# Jetson_power.net
KiCad netlist of a schematic drawn in Altium Designer
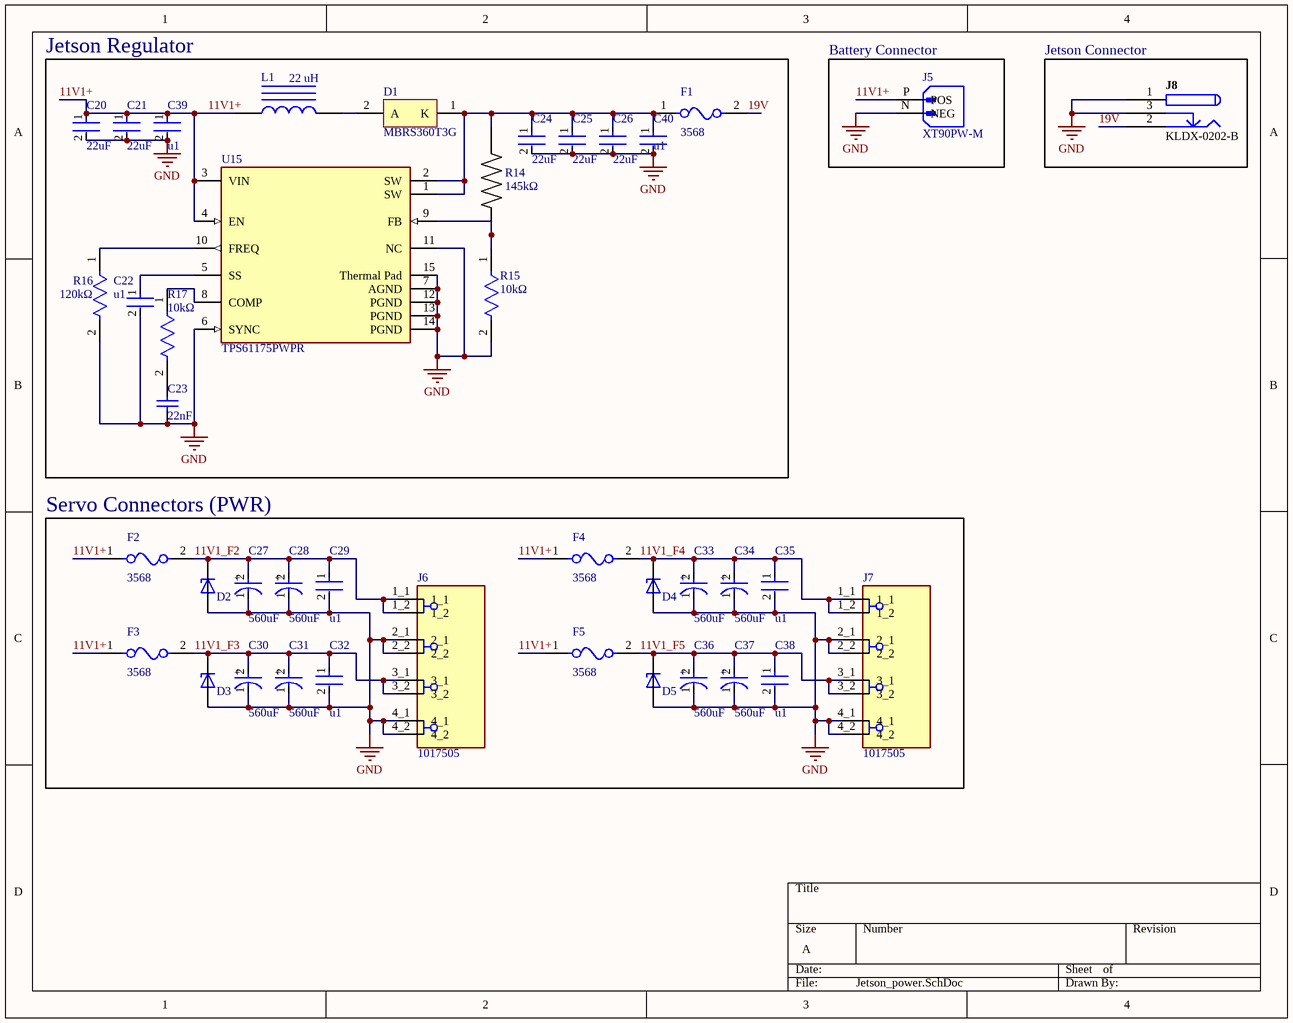
[diagram p0: Jetson_power.SchDoc]

(export (version "E")
  (design (tool "Eeschema 10.0.6"))
  (components
    (comp (ref "C20")
      (value "22uF")
      (footprint "FP-CGA9P-MFG")
      (description "CAP 2220 X7R 50V 22UF 20% 2.50MM CGA9P3X7R1H226M250KB")
      (libsource (lib "Altium Content Vault") (part "b4654b650e69147ec39a6b967a45e02"))
    )
    (comp (ref "C21")
      (value "22uF")
      (footprint "FP-CGA9P-MFG")
      (description "CAP 2220 X7R 50V 22UF 20% 2.50MM CGA9P3X7R1H226M250KB")
      (libsource (lib "Altium Content Vault") (part "b4654b650e69147ec39a6b967a45e02"))
    )
    (comp (ref "C22")
      (value "u1")
      (footprint "FP-CC0805-0_85-MFG")
      (description "CC0805KRX7R9BB104 CAP CER 0.1UF 50V X7R 0805")
      (fields (field (name "TOLERANCE") "0.1") (field (name "MANUFACTURER PART NUMBER") "CC0805KRX7R9BB104"))
      (libsource (lib "Altium Content Vault") (part "11868f565c42a9108669ba33697ecf6"))
    )
    (comp (ref "C23")
      (value "22nF")
      (footprint "CAPC2013X94X50ML20T25")
      (description "08055C223KAZ2A")
      (fields (field (name "MANUFACTURER") "AVX Interconnect / Elco"))
      (libsource (lib "Altium Content Vault") (part "CAP"))
    )
    (comp (ref "C24")
      (value "22uF")
      (footprint "FP-CGA9P-MFG")
      (description "CAP 2220 X7R 50V 22UF 20% 2.50MM CGA9P3X7R1H226M250KB")
      (libsource (lib "Altium Content Vault") (part "b4654b650e69147ec39a6b967a45e02"))
    )
    (comp (ref "C25")
      (value "22uF")
      (footprint "FP-CGA9P-MFG")
      (description "CAP 2220 X7R 50V 22UF 20% 2.50MM CGA9P3X7R1H226M250KB")
      (libsource (lib "Altium Content Vault") (part "b4654b650e69147ec39a6b967a45e02"))
    )
    (comp (ref "C26")
      (value "22uF")
      (footprint "FP-CGA9P-MFG")
      (description "CAP 2220 X7R 50V 22UF 20% 2.50MM CGA9P3X7R1H226M250KB")
      (libsource (lib "Altium Content Vault") (part "b4654b650e69147ec39a6b967a45e02"))
    )
    (comp (ref "C27")
      (value "560uF")
      (footprint "FP-OS-CON-TH-E12-d_0_6-MFG")
      (description "Conductive Polymer Aluminum Solid Capacitors (OS-CON) 560uF ±20% 16V RADIAL TH 8x12mm 16SEPF560M")
      (fields (field (name "TOLERANCE") "20%") (field (name "VOLTAGE") "16V"))
      (libsource (lib "Altium Content Vault") (part "203bc49f2ac43e59fd269a8c329ed05"))
    )
    (comp (ref "C28")
      (value "560uF")
      (footprint "FP-OS-CON-TH-E12-d_0_6-MFG")
      (description "Conductive Polymer Aluminum Solid Capacitors (OS-CON) 560uF ±20% 16V RADIAL TH 8x12mm 16SEPF560M")
      (fields (field (name "TOLERANCE") "20%") (field (name "VOLTAGE") "16V"))
      (libsource (lib "Altium Content Vault") (part "203bc49f2ac43e59fd269a8c329ed05"))
    )
    (comp (ref "C29")
      (value "u1")
      (footprint "FP-CC0805-0_85-MFG")
      (description "CC0805KRX7R9BB104 CAP CER 0.1UF 50V X7R 0805")
      (fields (field (name "TOLERANCE") "0.1") (field (name "MANUFACTURER PART NUMBER") "CC0805KRX7R9BB104"))
      (libsource (lib "Altium Content Vault") (part "11868f565c42a9108669ba33697ecf6"))
    )
    (comp (ref "C30")
      (value "560uF")
      (footprint "FP-OS-CON-TH-E12-d_0_6-MFG")
      (description "Conductive Polymer Aluminum Solid Capacitors (OS-CON) 560uF ±20% 16V RADIAL TH 8x12mm 16SEPF560M")
      (fields (field (name "TOLERANCE") "20%") (field (name "VOLTAGE") "16V"))
      (libsource (lib "Altium Content Vault") (part "203bc49f2ac43e59fd269a8c329ed05"))
    )
    (comp (ref "C31")
      (value "560uF")
      (footprint "FP-OS-CON-TH-E12-d_0_6-MFG")
      (description "Conductive Polymer Aluminum Solid Capacitors (OS-CON) 560uF ±20% 16V RADIAL TH 8x12mm 16SEPF560M")
      (fields (field (name "TOLERANCE") "20%") (field (name "VOLTAGE") "16V"))
      (libsource (lib "Altium Content Vault") (part "203bc49f2ac43e59fd269a8c329ed05"))
    )
    (comp (ref "C32")
      (value "u1")
      (footprint "FP-CC0805-0_85-MFG")
      (description "CC0805KRX7R9BB104 CAP CER 0.1UF 50V X7R 0805")
      (fields (field (name "TOLERANCE") "0.1") (field (name "MANUFACTURER PART NUMBER") "CC0805KRX7R9BB104"))
      (libsource (lib "Altium Content Vault") (part "11868f565c42a9108669ba33697ecf6"))
    )
    (comp (ref "C33")
      (value "560uF")
      (footprint "FP-OS-CON-TH-E12-d_0_6-MFG")
      (description "Conductive Polymer Aluminum Solid Capacitors (OS-CON) 560uF ±20% 16V RADIAL TH 8x12mm 16SEPF560M")
      (fields (field (name "TOLERANCE") "20%") (field (name "VOLTAGE") "16V"))
      (libsource (lib "Altium Content Vault") (part "203bc49f2ac43e59fd269a8c329ed05"))
    )
    (comp (ref "C34")
      (value "560uF")
      (footprint "FP-OS-CON-TH-E12-d_0_6-MFG")
      (description "Conductive Polymer Aluminum Solid Capacitors (OS-CON) 560uF ±20% 16V RADIAL TH 8x12mm 16SEPF560M")
      (fields (field (name "TOLERANCE") "20%") (field (name "VOLTAGE") "16V"))
      (libsource (lib "Altium Content Vault") (part "203bc49f2ac43e59fd269a8c329ed05"))
    )
    (comp (ref "C35")
      (value "u1")
      (footprint "FP-CC0805-0_85-MFG")
      (description "CC0805KRX7R9BB104 CAP CER 0.1UF 50V X7R 0805")
      (fields (field (name "TOLERANCE") "0.1") (field (name "MANUFACTURER PART NUMBER") "CC0805KRX7R9BB104"))
      (libsource (lib "Altium Content Vault") (part "11868f565c42a9108669ba33697ecf6"))
    )
    (comp (ref "C36")
      (value "560uF")
      (footprint "FP-OS-CON-TH-E12-d_0_6-MFG")
      (description "Conductive Polymer Aluminum Solid Capacitors (OS-CON) 560uF ±20% 16V RADIAL TH 8x12mm 16SEPF560M")
      (fields (field (name "TOLERANCE") "20%") (field (name "VOLTAGE") "16V"))
      (libsource (lib "Altium Content Vault") (part "203bc49f2ac43e59fd269a8c329ed05"))
    )
    (comp (ref "C37")
      (value "560uF")
      (footprint "FP-OS-CON-TH-E12-d_0_6-MFG")
      (description "Conductive Polymer Aluminum Solid Capacitors (OS-CON) 560uF ±20% 16V RADIAL TH 8x12mm 16SEPF560M")
      (fields (field (name "TOLERANCE") "20%") (field (name "VOLTAGE") "16V"))
      (libsource (lib "Altium Content Vault") (part "203bc49f2ac43e59fd269a8c329ed05"))
    )
    (comp (ref "C38")
      (value "u1")
      (footprint "FP-CC0805-0_85-MFG")
      (description "CC0805KRX7R9BB104 CAP CER 0.1UF 50V X7R 0805")
      (fields (field (name "TOLERANCE") "0.1") (field (name "MANUFACTURER PART NUMBER") "CC0805KRX7R9BB104"))
      (libsource (lib "Altium Content Vault") (part "11868f565c42a9108669ba33697ecf6"))
    )
    (comp (ref "C39")
      (value "u1")
      (footprint "FP-CC0805-0_85-MFG")
      (description "CC0805KRX7R9BB104 CAP CER 0.1UF 50V X7R 0805")
      (fields (field (name "TOLERANCE") "0.1") (field (name "MANUFACTURER PART NUMBER") "CC0805KRX7R9BB104"))
      (libsource (lib "Altium Content Vault") (part "11868f565c42a9108669ba33697ecf6"))
    )
    (comp (ref "C40")
      (value "u1")
      (footprint "FP-CC0805-0_85-MFG")
      (description "CC0805KRX7R9BB104 CAP CER 0.1UF 50V X7R 0805")
      (fields (field (name "TOLERANCE") "0.1") (field (name "MANUFACTURER PART NUMBER") "CC0805KRX7R9BB104"))
      (libsource (lib "Altium Content Vault") (part "11868f565c42a9108669ba33697ecf6"))
    )
    (comp (ref "D1")
      (value "MBRS360T3G")
      (footprint "ONSC-SMC-2-403-03_V")
      (description "Schottky Power Rectifier, 2-Pin SMC, Pb-Free, Tape and Reel")
      (fields (field (name "MANUFACTURER") "On Semiconductor"))
      (libsource (lib "Altium Content Vault") (part "ONSC-D-K1A2-2_A"))
    )
    (comp (ref "D2")
      (value "SMBJ13A-13-F")
      (footprint "DIOM5336X250N")
      (description "400 W 13 V Uni-Directional SMT Transient Voltage Suppressor Diode - DO-214AA")
      (fields (field (name "MF") "Diodes Inc."))
      (libsource (lib "Bryan Heddle") (part "SMBJ13A-13-F"))
    )
    (comp (ref "D3")
      (value "SMBJ13A-13-F")
      (footprint "DIOM5336X250N")
      (description "400 W 13 V Uni-Directional SMT Transient Voltage Suppressor Diode - DO-214AA")
      (fields (field (name "MF") "Diodes Inc."))
      (libsource (lib "Bryan Heddle") (part "SMBJ13A-13-F"))
    )
    (comp (ref "D4")
      (value "SMBJ13A-13-F")
      (footprint "DIOM5336X250N")
      (description "400 W 13 V Uni-Directional SMT Transient Voltage Suppressor Diode - DO-214AA")
      (fields (field (name "MF") "Diodes Inc."))
      (libsource (lib "Bryan Heddle") (part "SMBJ13A-13-F"))
    )
    (comp (ref "D5")
      (value "SMBJ13A-13-F")
      (footprint "DIOM5336X250N")
      (description "400 W 13 V Uni-Directional SMT Transient Voltage Suppressor Diode - DO-214AA")
      (fields (field (name "MF") "Diodes Inc."))
      (libsource (lib "Bryan Heddle") (part "SMBJ13A-13-F"))
    )
    (comp (ref "F1")
      (value "3568")
      (footprint "FP-3568-MFG")
      (fields (field (name "VOLTAGE") "500V"))
      (libsource (lib "Altium Content Vault") (part "3568"))
    )
    (comp (ref "F2")
      (value "3568")
      (footprint "FP-3568-MFG")
      (fields (field (name "VOLTAGE") "500V"))
      (libsource (lib "Altium Content Vault") (part "3568"))
    )
    (comp (ref "F3")
      (value "3568")
      (footprint "FP-3568-MFG")
      (fields (field (name "VOLTAGE") "500V"))
      (libsource (lib "Altium Content Vault") (part "3568"))
    )
    (comp (ref "F4")
      (value "3568")
      (footprint "FP-3568-MFG")
      (fields (field (name "VOLTAGE") "500V"))
      (libsource (lib "Altium Content Vault") (part "3568"))
    )
    (comp (ref "F5")
      (value "3568")
      (footprint "FP-3568-MFG")
      (fields (field (name "VOLTAGE") "500V"))
      (libsource (lib "Altium Content Vault") (part "3568"))
    )
    (comp (ref "J5")
      (value "XT90PW-M")
      (footprint "AMASS_XT90PW-M - duplicate")
      (description "Socket; DC supply; XT90; male; PIN: 2; on PCBs; THT; Colour: yellow")
      (fields (field (name "MF") "AMASS"))
      (libsource (lib "AI_Project_Library") (part "XT90PW-M"))
    )
    (comp (ref "J6")
      (value "1017505")
      (footprint "PHOENIX_1017505")
      (fields (field (name "MF") "{'manufacturer': u'Phoenix Contact'}"))
      (libsource (lib "Bryan Heddle") (part "1017505"))
    )
    (comp (ref "J7")
      (value "1017505")
      (footprint "PHOENIX_1017505")
      (fields (field (name "MF") "{'manufacturer': u'Phoenix Contact'}"))
      (libsource (lib "Bryan Heddle") (part "1017505"))
    )
    (comp (ref "J8")
      (value "KLDX-0202-B")
      (footprint "KYCN-KLDX-0202-B_V")
      (description "3 Conductor Power Jack, 2 break 2 aux contacts")
      (libsource (lib "Altium Content Vault") (part "KYCN-KLDX-0202-B-3"))
    )
    (comp (ref "L1")
      (value "22 uH")
      (footprint "COIL-MSS1038_V")
      (description "XAL7070")
      (fields (field (name "TOLERANCE") "20%") (field (name "MANUFACTURER") "Coilcraft"))
      (libsource (lib "Altium Content Vault") (part "IND-DOT-2_A"))
    )
    (comp (ref "R14")
      (value "145kΩ")
      (footprint "*RESC2012X60N")
      (description "RN73H2ATTD1453B25")
      (libsource (lib "AI_Project_Library") (part "RN73H2ATTD1453B25"))
    )
    (comp (ref "R15")
      (value "10kΩ")
      (footprint "FP-RNCP0805-IPC_C")
      (description "10kΩ ±1% 0.25W 0805 High Power Anti-Sulfur Thin Film Chip Resistor RNCP0805FTD10K0")
      (fields (field (name "TOLERANCE") "1%"))
      (libsource (lib "Altium Content Vault") (part "1029c3af85768c4190bb7ad29bc67b5"))
    )
    (comp (ref "R16")
      (value "120kΩ")
      (footprint "FP-RMCF0603-IPC_A")
      (description "120kΩ ±1% 0.1W 0603 Thick Film Chip Resistor AEC-Q200 compliant RMCF0603FG120K")
      (fields (field (name "TOLERANCE") "1%"))
      (libsource (lib "Altium Content Vault") (part "1029c3af85768c4190bb7ad29bc67b5"))
    )
    (comp (ref "R17")
      (value "10kΩ")
      (footprint "FP-RNCP0805-IPC_C")
      (description "10kΩ ±1% 0.25W 0805 High Power Anti-Sulfur Thin Film Chip Resistor RNCP0805FTD10K0")
      (fields (field (name "TOLERANCE") "1%"))
      (libsource (lib "Altium Content Vault") (part "1029c3af85768c4190bb7ad29bc67b5"))
    )
    (comp (ref "U15")
      (value "TPS61175PWPR")
      (footprint "FP-PWP0014E-MFG")
      (description "IC REG MULT CONFIG ADJ 14HTSSOP")
      (fields
        (field (name "OCTOPART") "https://octopart.com/tps61175pwpr-texas+instruments-12190773")
        (field (name "MANUFACTURER") "Texas Instruments")
      )
      (libsource (lib "Altium Content Vault") (part "f47c98dbe7414c9a8c87baa7f0ed8c9"))
    )
  )
  (nets
    (net (code "1") (name "/11V1+") (class "Default")
      (node (ref "C20") (pin "1") (pinfunction "1_1") (pintype "passive"))
      (node (ref "C21") (pin "1") (pinfunction "1_1") (pintype "passive"))
      (node (ref "C39") (pin "1") (pinfunction "1_1") (pintype "passive"))
      (node (ref "F2") (pin "1") (pinfunction "1_1") (pintype "passive"))
      (node (ref "F3") (pin "1") (pinfunction "1_1") (pintype "passive"))
      (node (ref "F4") (pin "1") (pinfunction "1_1") (pintype "passive"))
      (node (ref "F5") (pin "1") (pinfunction "1_1") (pintype "passive"))
      (node (ref "J5") (pin "P") (pinfunction "POS_P") (pintype "passive"))
      (node (ref "L1") (pin "1") (pinfunction "1_1") (pintype "passive"))
      (node (ref "U15") (pin "3") (pinfunction "VIN_3") (pintype "power_in"))
      (node (ref "U15") (pin "4") (pinfunction "EN_4") (pintype "input"))
    )
    (net (code "2") (name "/11V1_F2") (class "Default")
      (node (ref "C27") (pin "2") (pinfunction "A_2") (pintype "passive"))
      (node (ref "C28") (pin "2") (pinfunction "A_2") (pintype "passive"))
      (node (ref "C29") (pin "1") (pinfunction "1_1") (pintype "passive"))
      (node (ref "D2") (pin "1") (pinfunction "C_1") (pintype "passive"))
      (node (ref "F2") (pin "2") (pinfunction "2_2") (pintype "passive"))
      (node (ref "J6") (pin "1_1") (pinfunction "1_1_1_1") (pintype "passive"))
      (node (ref "J6") (pin "1_2") (pinfunction "1_2_1_2") (pintype "passive"))
    )
    (net (code "3") (name "/11V1_F3") (class "Default")
      (node (ref "C30") (pin "2") (pinfunction "A_2") (pintype "passive"))
      (node (ref "C31") (pin "2") (pinfunction "A_2") (pintype "passive"))
      (node (ref "C32") (pin "1") (pinfunction "1_1") (pintype "passive"))
      (node (ref "D3") (pin "1") (pinfunction "C_1") (pintype "passive"))
      (node (ref "F3") (pin "2") (pinfunction "2_2") (pintype "passive"))
      (node (ref "J6") (pin "3_1") (pinfunction "3_1_3_1") (pintype "passive"))
      (node (ref "J6") (pin "3_2") (pinfunction "3_2_3_2") (pintype "passive"))
    )
    (net (code "4") (name "/11V1_F4") (class "Default")
      (node (ref "C33") (pin "2") (pinfunction "A_2") (pintype "passive"))
      (node (ref "C34") (pin "2") (pinfunction "A_2") (pintype "passive"))
      (node (ref "C35") (pin "1") (pinfunction "1_1") (pintype "passive"))
      (node (ref "D4") (pin "1") (pinfunction "C_1") (pintype "passive"))
      (node (ref "F4") (pin "2") (pinfunction "2_2") (pintype "passive"))
      (node (ref "J7") (pin "1_1") (pinfunction "1_1_1_1") (pintype "passive"))
      (node (ref "J7") (pin "1_2") (pinfunction "1_2_1_2") (pintype "passive"))
    )
    (net (code "5") (name "/11V1_F5") (class "Default")
      (node (ref "C36") (pin "2") (pinfunction "A_2") (pintype "passive"))
      (node (ref "C37") (pin "2") (pinfunction "A_2") (pintype "passive"))
      (node (ref "C38") (pin "1") (pinfunction "1_1") (pintype "passive"))
      (node (ref "D5") (pin "1") (pinfunction "C_1") (pintype "passive"))
      (node (ref "F5") (pin "2") (pinfunction "2_2") (pintype "passive"))
      (node (ref "J7") (pin "3_1") (pinfunction "3_1_3_1") (pintype "passive"))
      (node (ref "J7") (pin "3_2") (pinfunction "3_2_3_2") (pintype "passive"))
    )
    (net (code "6") (name "/19V") (class "Default")
      (node (ref "F1") (pin "2") (pinfunction "2_2") (pintype "passive"))
      (node (ref "J8") (pin "2") (pintype "power_in"))
    )
    (net (code "7") (name "GND") (class "Default")
      (node (ref "C20") (pin "2") (pinfunction "2_2") (pintype "passive"))
      (node (ref "C21") (pin "2") (pinfunction "2_2") (pintype "passive"))
      (node (ref "C22") (pin "2") (pinfunction "2_2") (pintype "passive"))
      (node (ref "C23") (pin "1") (pinfunction "1_1") (pintype "passive"))
      (node (ref "C24") (pin "2") (pinfunction "2_2") (pintype "passive"))
      (node (ref "C25") (pin "2") (pinfunction "2_2") (pintype "passive"))
      (node (ref "C26") (pin "2") (pinfunction "2_2") (pintype "passive"))
      (node (ref "C27") (pin "1") (pinfunction "C_1") (pintype "passive"))
      (node (ref "C28") (pin "1") (pinfunction "C_1") (pintype "passive"))
      (node (ref "C29") (pin "2") (pinfunction "2_2") (pintype "passive"))
      (node (ref "C30") (pin "1") (pinfunction "C_1") (pintype "passive"))
      (node (ref "C31") (pin "1") (pinfunction "C_1") (pintype "passive"))
      (node (ref "C32") (pin "2") (pinfunction "2_2") (pintype "passive"))
      (node (ref "C33") (pin "1") (pinfunction "C_1") (pintype "passive"))
      (node (ref "C34") (pin "1") (pinfunction "C_1") (pintype "passive"))
      (node (ref "C35") (pin "2") (pinfunction "2_2") (pintype "passive"))
      (node (ref "C36") (pin "1") (pinfunction "C_1") (pintype "passive"))
      (node (ref "C37") (pin "1") (pinfunction "C_1") (pintype "passive"))
      (node (ref "C38") (pin "2") (pinfunction "2_2") (pintype "passive"))
      (node (ref "C39") (pin "2") (pinfunction "2_2") (pintype "passive"))
      (node (ref "C40") (pin "2") (pinfunction "2_2") (pintype "passive"))
      (node (ref "D2") (pin "2") (pinfunction "A_2") (pintype "passive"))
      (node (ref "D3") (pin "2") (pinfunction "A_2") (pintype "passive"))
      (node (ref "D4") (pin "2") (pinfunction "A_2") (pintype "passive"))
      (node (ref "D5") (pin "2") (pinfunction "A_2") (pintype "passive"))
      (node (ref "J5") (pin "N") (pinfunction "NEG_N") (pintype "passive"))
      (node (ref "J6") (pin "2_1") (pinfunction "2_1_2_1") (pintype "passive"))
      (node (ref "J6") (pin "2_2") (pinfunction "2_2_2_2") (pintype "passive"))
      (node (ref "J6") (pin "4_1") (pinfunction "4_1_4_1") (pintype "passive"))
      (node (ref "J6") (pin "4_2") (pinfunction "4_2_4_2") (pintype "passive"))
      (node (ref "J7") (pin "2_1") (pinfunction "2_1_2_1") (pintype "passive"))
      (node (ref "J7") (pin "2_2") (pinfunction "2_2_2_2") (pintype "passive"))
      (node (ref "J7") (pin "4_1") (pinfunction "4_1_4_1") (pintype "passive"))
      (node (ref "J7") (pin "4_2") (pinfunction "4_2_4_2") (pintype "passive"))
      (node (ref "J8") (pin "1") (pintype "power_in"))
      (node (ref "J8") (pin "3") (pintype "power_in"))
      (node (ref "R15") (pin "2") (pinfunction "2_2") (pintype "passive"))
      (node (ref "R16") (pin "2") (pinfunction "2_2") (pintype "passive"))
      (node (ref "U15") (pin "11") (pinfunction "NC_11") (pintype "passive"))
      (node (ref "U15") (pin "12") (pinfunction "PGND_12") (pintype "power_in"))
      (node (ref "U15") (pin "13") (pinfunction "PGND_13") (pintype "power_in"))
      (node (ref "U15") (pin "14") (pinfunction "PGND_14") (pintype "power_in"))
      (node (ref "U15") (pin "15") (pinfunction "Thermal_Pad_15") (pintype "power_in"))
      (node (ref "U15") (pin "6") (pinfunction "SYNC_6") (pintype "input"))
      (node (ref "U15") (pin "7") (pinfunction "AGND_7") (pintype "power_in"))
    )
    (net (code "8") (name "Net-(C23-Pad2)") (class "Default")
      (node (ref "C23") (pin "2") (pinfunction "2_2") (pintype "passive"))
      (node (ref "R17") (pin "2") (pinfunction "2_2") (pintype "passive"))
    )
    (net (code "9") (name "Net-(D1-A)") (class "Default")
      (node (ref "D1") (pin "2") (pinfunction "A_2") (pintype "passive"))
      (node (ref "L1") (pin "2") (pinfunction "2_2") (pintype "passive"))
    )
    (net (code "10") (name "Net-(D1-K)") (class "Default")
      (node (ref "C24") (pin "1") (pinfunction "1_1") (pintype "passive"))
      (node (ref "C25") (pin "1") (pinfunction "1_1") (pintype "passive"))
      (node (ref "C26") (pin "1") (pinfunction "1_1") (pintype "passive"))
      (node (ref "C40") (pin "1") (pinfunction "1_1") (pintype "passive"))
      (node (ref "D1") (pin "1") (pinfunction "K_1") (pintype "passive"))
      (node (ref "F1") (pin "1") (pinfunction "1_1") (pintype "passive"))
      (node (ref "R14") (pin "1") (pinfunction "1_1") (pintype "passive"))
      (node (ref "U15") (pin "1") (pinfunction "SW_1") (pintype "power_in"))
      (node (ref "U15") (pin "2") (pinfunction "SW_2") (pintype "power_in"))
    )
    (net (code "11") (name "Net-(U15-COMP)") (class "Default")
      (node (ref "R17") (pin "1") (pinfunction "1_1") (pintype "passive"))
      (node (ref "U15") (pin "8") (pinfunction "COMP_8") (pintype "passive"))
    )
    (net (code "12") (name "Net-(U15-FB)") (class "Default")
      (node (ref "R14") (pin "2") (pinfunction "2_2") (pintype "passive"))
      (node (ref "R15") (pin "1") (pinfunction "1_1") (pintype "passive"))
      (node (ref "U15") (pin "9") (pinfunction "FB_9") (pintype "input"))
    )
    (net (code "13") (name "Net-(U15-FREQ)") (class "Default")
      (node (ref "R16") (pin "1") (pinfunction "1_1") (pintype "passive"))
      (node (ref "U15") (pin "10") (pinfunction "FREQ_10") (pintype "output"))
    )
    (net (code "14") (name "Net-(U15-SS)") (class "Default")
      (node (ref "C22") (pin "1") (pinfunction "1_1") (pintype "passive"))
      (node (ref "U15") (pin "5") (pinfunction "SS_5") (pintype "passive"))
    )
  )
)
